# Versterker.net
KiCad netlist of a schematic drawn in Altium Designer
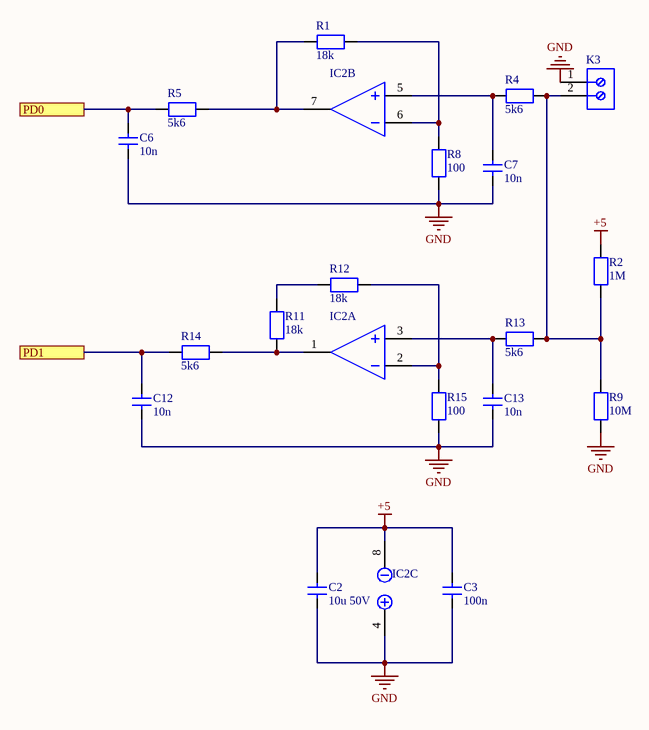
[diagram p0: Versterker.SchDoc]

(export (version "E")
  (design (tool "Eeschema 10.0.6"))
  (components
    (comp (ref "C2")
      (value "10u 50V")
      (footprint "Capacitor10uf")
      (description "CAP CER 10000PF 50V X7R 0805")
      (fields (field (name "TOLERANCE") "10%"))
      (libsource (lib "Soldeerstation Schematic") (part "Capacitor"))
    )
    (comp (ref "C3")
      (value "100n")
      (footprint "Capacitor100nf")
      (description "CAP CER 10000PF 50V X7R 0805")
      (fields (field (name "TOLERANCE") "10%"))
      (libsource (lib "Soldeerstation Schematic") (part "Capacitor"))
    )
    (comp (ref "C6")
      (value "10n")
      (footprint "CAPACITOR10NF")
      (description "CAP CER 10000PF 50V X7R 0805")
      (fields (field (name "TOLERANCE") "10%"))
      (libsource (lib "Soldeerstation Schematic") (part "Capacitor"))
    )
    (comp (ref "C7")
      (value "10n")
      (footprint "CAPACITOR10NF")
      (description "CAP CER 10000PF 50V X7R 0805")
      (fields (field (name "TOLERANCE") "10%"))
      (libsource (lib "Soldeerstation Schematic") (part "Capacitor"))
    )
    (comp (ref "C12")
      (value "10n")
      (footprint "CAPACITOR10NF")
      (description "CAP CER 10000PF 50V X7R 0805")
      (fields (field (name "TOLERANCE") "10%"))
      (libsource (lib "Soldeerstation Schematic") (part "Capacitor"))
    )
    (comp (ref "C13")
      (value "10n")
      (footprint "CAPACITOR10NF")
      (description "CAP CER 10000PF 50V X7R 0805")
      (fields (field (name "TOLERANCE") "10%"))
      (libsource (lib "Soldeerstation Schematic") (part "Capacitor"))
    )
    (comp (ref "IC2")
      (value "~")
      (footprint "Opamp")
      (description "None")
      (libsource (lib "Soldeerstation Schematic") (part "Opamp"))
    )
    (comp (ref "K3")
      (value "~")
      (footprint "Shroefconnecter")
      (description "Female Header, Pitch 5 mm, 1 x 2 Position, Height 10 mm, Tail Length 3.5 mm, Rohs, Bulk")
      (fields (field (name "VOLTAGE") "300V") (field (name "MANUFACTURER") "TE Connectivity"))
      (libsource (lib "Soldeerstation Schematic") (part "Schroefconnector"))
    )
    (comp (ref "R1")
      (value "18k")
      (footprint "Resistor")
      (fields (field (name "MANUFACTURER") "Vishay Dale") (field (name "PART NUMBER") "CRCW08050000Z0EA"))
      (libsource (lib "Soldeerstation Schematic") (part "Resistor"))
    )
    (comp (ref "R2")
      (value "1M")
      (footprint "Resistor")
      (fields (field (name "MANUFACTURER") "Vishay Dale") (field (name "PART NUMBER") "CRCW08050000Z0EA"))
      (libsource (lib "Soldeerstation Schematic") (part "Resistor"))
    )
    (comp (ref "R4")
      (value "5k6")
      (footprint "Resistor")
      (fields (field (name "MANUFACTURER") "Vishay Dale") (field (name "PART NUMBER") "CRCW08050000Z0EA"))
      (libsource (lib "Soldeerstation Schematic") (part "Resistor"))
    )
    (comp (ref "R5")
      (value "5k6")
      (footprint "Resistor")
      (fields (field (name "MANUFACTURER") "Vishay Dale") (field (name "PART NUMBER") "CRCW08050000Z0EA"))
      (libsource (lib "Soldeerstation Schematic") (part "Resistor"))
    )
    (comp (ref "R8")
      (value "100")
      (footprint "Resistor")
      (fields (field (name "MANUFACTURER") "Vishay Dale") (field (name "PART NUMBER") "CRCW08050000Z0EA"))
      (libsource (lib "Soldeerstation Schematic") (part "Resistor"))
    )
    (comp (ref "R9")
      (value "10M")
      (footprint "Resistor")
      (fields (field (name "MANUFACTURER") "Vishay Dale") (field (name "PART NUMBER") "CRCW08050000Z0EA"))
      (libsource (lib "Soldeerstation Schematic") (part "Resistor"))
    )
    (comp (ref "R11")
      (value "18k")
      (footprint "Resistor")
      (fields (field (name "MANUFACTURER") "Vishay Dale") (field (name "PART NUMBER") "CRCW08050000Z0EA"))
      (libsource (lib "Soldeerstation Schematic") (part "Resistor"))
    )
    (comp (ref "R12")
      (value "18k")
      (footprint "Resistor")
      (fields (field (name "MANUFACTURER") "Vishay Dale") (field (name "PART NUMBER") "CRCW08050000Z0EA"))
      (libsource (lib "Soldeerstation Schematic") (part "Resistor"))
    )
    (comp (ref "R13")
      (value "5k6")
      (footprint "Resistor")
      (fields (field (name "MANUFACTURER") "Vishay Dale") (field (name "PART NUMBER") "CRCW08050000Z0EA"))
      (libsource (lib "Soldeerstation Schematic") (part "Resistor"))
    )
    (comp (ref "R14")
      (value "5k6")
      (footprint "Resistor")
      (fields (field (name "MANUFACTURER") "Vishay Dale") (field (name "PART NUMBER") "CRCW08050000Z0EA"))
      (libsource (lib "Soldeerstation Schematic") (part "Resistor"))
    )
    (comp (ref "R15")
      (value "100")
      (footprint "Resistor")
      (fields (field (name "MANUFACTURER") "Vishay Dale") (field (name "PART NUMBER") "CRCW08050000Z0EA"))
      (libsource (lib "Soldeerstation Schematic") (part "Resistor"))
    )
  )
  (nets
    (net (code "1") (name "+5") (class "Default")
      (node (ref "C2") (pin "1") (pinfunction "1_1") (pintype "passive"))
      (node (ref "C3") (pin "1") (pinfunction "1_1") (pintype "passive"))
      (node (ref "IC2") (pin "8") (pintype "power_in"))
      (node (ref "R2") (pin "2") (pinfunction "2_2") (pintype "passive"))
    )
    (net (code "2") (name "/PD0") (class "Default")
      (node (ref "C6") (pin "2") (pinfunction "2_2") (pintype "passive"))
      (node (ref "R5") (pin "1") (pinfunction "1_1") (pintype "passive"))
    )
    (net (code "3") (name "/PD1") (class "Default")
      (node (ref "C12") (pin "2") (pinfunction "2_2") (pintype "passive"))
      (node (ref "R14") (pin "1") (pinfunction "1_1") (pintype "passive"))
    )
    (net (code "4") (name "GND") (class "Default")
      (node (ref "C12") (pin "1") (pinfunction "1_1") (pintype "passive"))
      (node (ref "C13") (pin "1") (pinfunction "1_1") (pintype "passive"))
      (node (ref "C2") (pin "2") (pinfunction "2_2") (pintype "passive"))
      (node (ref "C3") (pin "2") (pinfunction "2_2") (pintype "passive"))
      (node (ref "C6") (pin "1") (pinfunction "1_1") (pintype "passive"))
      (node (ref "C7") (pin "1") (pinfunction "1_1") (pintype "passive"))
      (node (ref "IC2") (pin "4") (pintype "power_in"))
      (node (ref "K3") (pin "1") (pinfunction "1_1") (pintype "passive"))
      (node (ref "R15") (pin "2") (pinfunction "2_2") (pintype "passive"))
      (node (ref "R8") (pin "1") (pinfunction "1_1") (pintype "passive"))
      (node (ref "R9") (pin "2") (pinfunction "2_2") (pintype "passive"))
    )
    (net (code "5") (name "Net-(IC2A-VINA+)") (class "Default")
      (node (ref "C13") (pin "2") (pinfunction "2_2") (pintype "passive"))
      (node (ref "IC2") (pin "3") (pinfunction "VINA+_3") (pintype "passive"))
      (node (ref "R13") (pin "1") (pinfunction "1_1") (pintype "passive"))
    )
    (net (code "6") (name "Net-(IC2A-VINA-)") (class "Default")
      (node (ref "IC2") (pin "2") (pinfunction "VINA-_2") (pintype "passive"))
      (node (ref "R12") (pin "2") (pinfunction "2_2") (pintype "passive"))
      (node (ref "R15") (pin "1") (pinfunction "1_1") (pintype "passive"))
    )
    (net (code "7") (name "Net-(IC2A-VOUTA)") (class "Default")
      (node (ref "IC2") (pin "1") (pinfunction "VOUTA_1") (pintype "passive"))
      (node (ref "R11") (pin "1") (pinfunction "1_1") (pintype "passive"))
      (node (ref "R14") (pin "2") (pinfunction "2_2") (pintype "passive"))
    )
    (net (code "8") (name "Net-(IC2B-VINB+)") (class "Default")
      (node (ref "C7") (pin "2") (pinfunction "2_2") (pintype "passive"))
      (node (ref "IC2") (pin "5") (pinfunction "VINB+_5") (pintype "passive"))
      (node (ref "R4") (pin "1") (pinfunction "1_1") (pintype "passive"))
    )
    (net (code "9") (name "Net-(IC2B-VINB-)") (class "Default")
      (node (ref "IC2") (pin "6") (pinfunction "VINB-_6") (pintype "passive"))
      (node (ref "R1") (pin "2") (pinfunction "2_2") (pintype "passive"))
      (node (ref "R8") (pin "2") (pinfunction "2_2") (pintype "passive"))
    )
    (net (code "10") (name "Net-(IC2B-VOUTB)") (class "Default")
      (node (ref "IC2") (pin "7") (pinfunction "VOUTB_7") (pintype "passive"))
      (node (ref "R1") (pin "1") (pinfunction "1_1") (pintype "passive"))
      (node (ref "R5") (pin "2") (pinfunction "2_2") (pintype "passive"))
    )
    (net (code "11") (name "Net-(K3-Pad2)") (class "Default")
      (node (ref "K3") (pin "2") (pinfunction "2_2") (pintype "passive"))
      (node (ref "R13") (pin "2") (pinfunction "2_2") (pintype "passive"))
      (node (ref "R2") (pin "1") (pinfunction "1_1") (pintype "passive"))
      (node (ref "R4") (pin "2") (pinfunction "2_2") (pintype "passive"))
      (node (ref "R9") (pin "1") (pinfunction "1_1") (pintype "passive"))
    )
    (net (code "12") (name "Net-(R11-Pad2)") (class "Default")
      (node (ref "R11") (pin "2") (pinfunction "2_2") (pintype "passive"))
      (node (ref "R12") (pin "1") (pinfunction "1_1") (pintype "passive"))
    )
  )
)
